# SAU-G0-EX_AHT-GL.net
KiCad netlist of a schematic drawn in Altium Designer
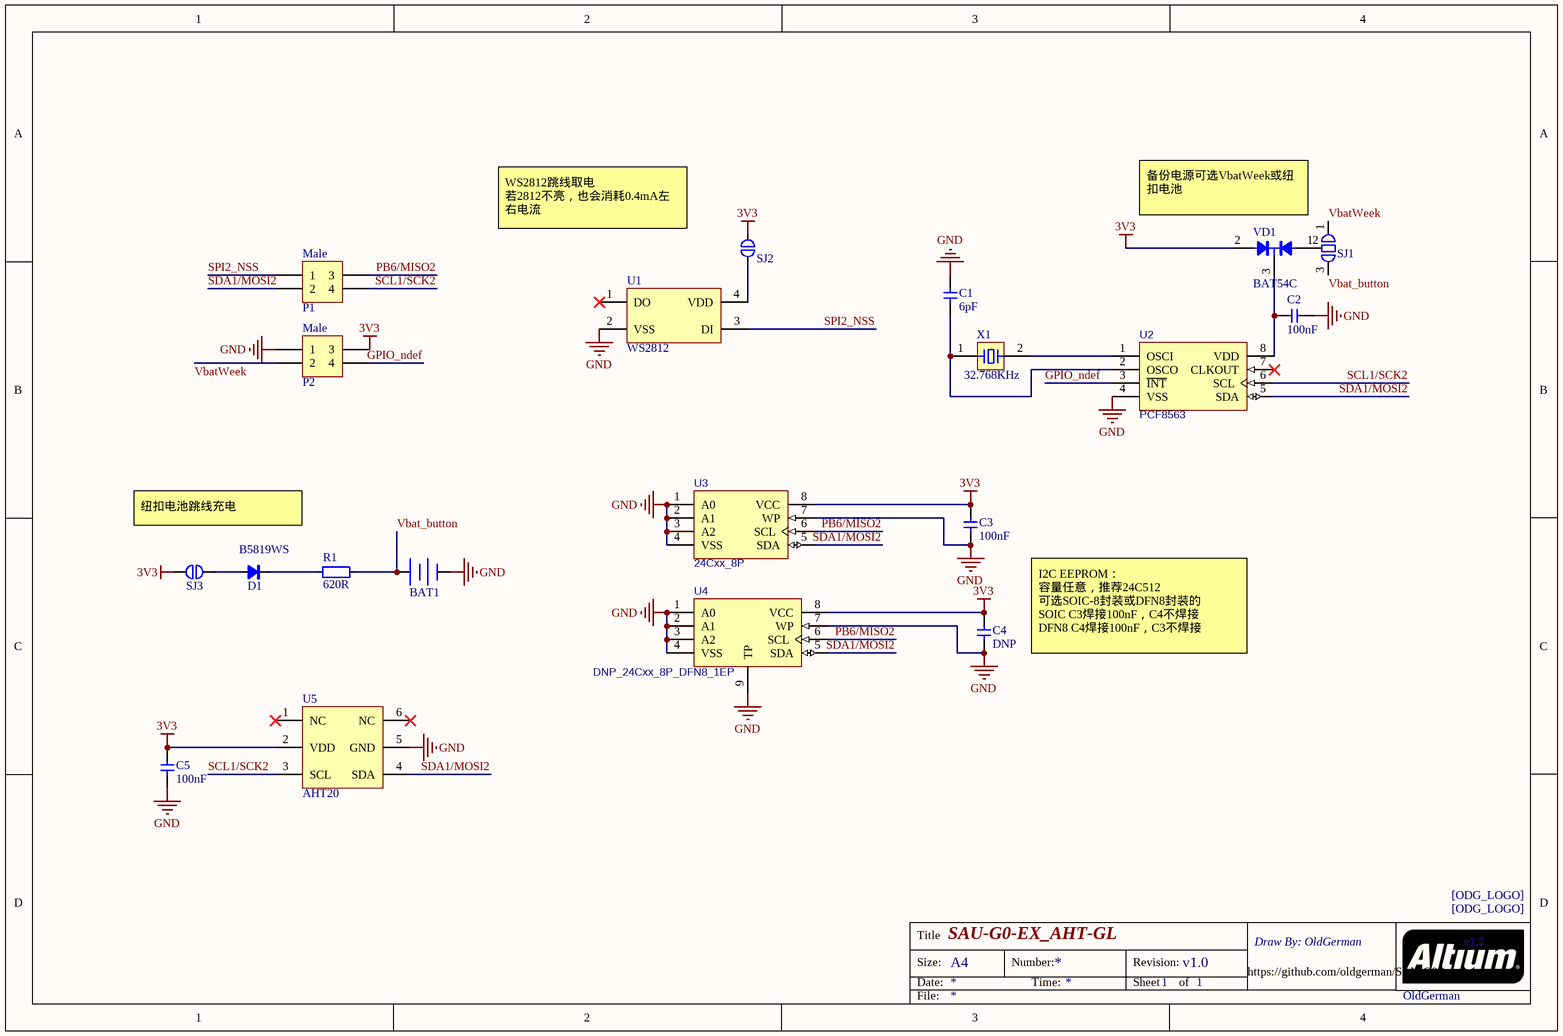
[diagram p0: SAU-G0-EX_AHT-GL.SchDoc]

(export (version "E")
  (design (tool "Eeschema 10.0.6"))
  (components
    (comp (ref "BAT1")
      (value "BAT")
      (footprint "MS621FE-FL11E")
      (description "锂电池")
      (libsource (lib "ODG_AD_Lib") (part "BAT"))
    )
    (comp (ref "C1")
      (value "6pF")
      (footprint "C0603")
      (description "Capacitor")
      (libsource (lib "ODG_AD_Lib") (part "CAP"))
    )
    (comp (ref "C2")
      (value "100nF")
      (footprint "C0603")
      (description "Capacitor")
      (libsource (lib "ODG_AD_Lib") (part "CAP"))
    )
    (comp (ref "C3")
      (value "100nF")
      (footprint "C0603")
      (description "Capacitor")
      (libsource (lib "ODG_AD_Lib") (part "CAP"))
    )
    (comp (ref "C4")
      (value "DNP")
      (footprint "C0402")
      (description "Capacitor")
      (libsource (lib "ODG_AD_Lib") (part "CAP"))
    )
    (comp (ref "C5")
      (value "100nF")
      (footprint "C0603")
      (description "Capacitor")
      (libsource (lib "ODG_AD_Lib") (part "CAP"))
    )
    (comp (ref "D1")
      (value "B5819WS")
      (footprint "SOD-323")
      (description "二极管")
      (libsource (lib "ODG_AD_Lib") (part "DIODE"))
    )
    (comp (ref "ODG1")
      (value "ODG_LOGO")
      (footprint "ODG_LOGO_soldermask")
      (libsource (lib "ODG_AD_Lib") (part "ODG_LOGO"))
    )
    (comp (ref "ODG2")
      (value "ODG_LOGO")
      (footprint "ODG_LOGO_soldermask")
      (libsource (lib "ODG_AD_Lib") (part "ODG_LOGO"))
    )
    (comp (ref "P1")
      (value "Male")
      (footprint "2.0mm_Male_2x2")
      (libsource (lib "ODG_AD_Lib") (part "CONN_2X2"))
    )
    (comp (ref "P2")
      (value "Male")
      (footprint "2.0mm_Male_2x2")
      (libsource (lib "ODG_AD_Lib") (part "CONN_2X2"))
    )
    (comp (ref "R1")
      (value "620R")
      (footprint "R0603")
      (description "Resistor")
      (libsource (lib "ODG_AD_Lib") (part "RES"))
    )
    (comp (ref "SJ1")
      (value "SJ_3P")
      (footprint "SJ_3P_MINI")
      (description "焊接跳线二选一")
      (libsource (lib "ODG_AD_Lib") (part "SJ_3P"))
    )
    (comp (ref "SJ2")
      (value "SJ_2P")
      (footprint "SJ_2P_MINI")
      (description "焊接跳线")
      (libsource (lib "ODG_AD_Lib") (part "SJ_2P"))
    )
    (comp (ref "SJ3")
      (value "SJ_2P")
      (footprint "SJ_2P_MINI")
      (description "焊接跳线")
      (libsource (lib "") (part "SJ_2P_1"))
    )
    (comp (ref "U1")
      (value "WS2812")
      (footprint "WS2812_2020")
      (libsource (lib "ODG_AD_Lib") (part "WS2812"))
    )
    (comp (ref "U2")
      (value "PCF8563")
      (footprint "ANALOG DEV SOIC-8 R8")
      (libsource (lib "ODG_AD_Lib") (part "PCF8563"))
    )
    (comp (ref "U3")
      (value "24Cxx_8P")
      (footprint "ANALOG DEV SOIC-8 R8")
      (libsource (lib "ODG_AD_Lib") (part "24Cxx_8P"))
    )
    (comp (ref "U4")
      (value "DNP_24Cxx_8P_DFN8_1EP")
      (footprint "DFN-8-1EP_3x2mm_P0.5mm_EP1.75x1.45mm")
      (libsource (lib "ODG_AD_Lib") (part "24Cxx_8P_DFN8_1EP"))
    )
    (comp (ref "U5")
      (value "AHT20")
      (footprint "AHT20")
      (description "线性稳压芯片")
      (fields (field (name "版权归属") "源创客"))
      (libsource (lib "ODG_AD_Lib") (part "AHT20"))
    )
    (comp (ref "VD1")
      (value "BAT54C")
      (footprint "DIODES SOT-323-3")
      (description "贴片肖特基二极管")
      (fields (field (name "版权归属") "源创客"))
      (libsource (lib "ODG_AD_Lib") (part "BAT54C"))
    )
    (comp (ref "X1")
      (value "32.768KHz")
      (footprint "XTAL_2P_3215")
      (description "2脚无源石英晶振")
      (fields (field (name "版权归属") "源创客"))
      (libsource (lib "ODG_AD_Lib") (part "XTAL-2P"))
    )
  )
  (nets
    (net (code "1") (name "/GPIO_ndef") (class "Default")
      (node (ref "P2") (pin "4") (pinfunction "4_4") (pintype "passive"))
      (node (ref "U2") (pin "3") (pinfunction "~{INT}_3") (pintype "passive"))
    )
    (net (code "2") (name "/PB6{slash}MISO2") (class "Default")
      (node (ref "P1") (pin "3") (pinfunction "3_3") (pintype "passive"))
      (node (ref "U3") (pin "6") (pinfunction "SCL_6") (pintype "input"))
      (node (ref "U4") (pin "6") (pinfunction "SCL_6") (pintype "input"))
    )
    (net (code "3") (name "/SCL1{slash}SCK2") (class "Default")
      (node (ref "P1") (pin "4") (pinfunction "4_4") (pintype "passive"))
      (node (ref "U2") (pin "6") (pinfunction "SCL_6") (pintype "input"))
      (node (ref "U5") (pin "3") (pinfunction "SCL_3") (pintype "passive"))
    )
    (net (code "4") (name "/SDA1{slash}MOSI2") (class "Default")
      (node (ref "P1") (pin "2") (pinfunction "2_2") (pintype "passive"))
      (node (ref "U2") (pin "5") (pinfunction "SDA_5") (pintype "bidirectional"))
      (node (ref "U3") (pin "5") (pinfunction "SDA_5") (pintype "bidirectional"))
      (node (ref "U4") (pin "5") (pinfunction "SDA_5") (pintype "bidirectional"))
      (node (ref "U5") (pin "4") (pinfunction "SDA_4") (pintype "passive"))
    )
    (net (code "5") (name "/SPI2_NSS") (class "Default")
      (node (ref "P1") (pin "1") (pinfunction "1_1") (pintype "passive"))
      (node (ref "U1") (pin "3") (pinfunction "DI_3") (pintype "passive"))
    )
    (net (code "6") (name "/VbatWeek") (class "Default")
      (node (ref "P2") (pin "2") (pinfunction "2_2") (pintype "passive"))
      (node (ref "SJ1") (pin "1") (pinfunction "1_1") (pintype "passive"))
    )
    (net (code "7") (name "/Vbat_button") (class "Default")
      (node (ref "BAT1") (pin "1") (pinfunction "+_1") (pintype "passive"))
      (node (ref "R1") (pin "2") (pinfunction "2_2") (pintype "passive"))
      (node (ref "SJ1") (pin "3") (pinfunction "3_3") (pintype "passive"))
    )
    (net (code "8") (name "3V3") (class "Default")
      (node (ref "C3") (pin "1") (pinfunction "1_1") (pintype "passive"))
      (node (ref "C4") (pin "1") (pinfunction "1_1") (pintype "passive"))
      (node (ref "C5") (pin "1") (pinfunction "1_1") (pintype "passive"))
      (node (ref "P2") (pin "3") (pinfunction "3_3") (pintype "passive"))
      (node (ref "SJ2") (pin "1") (pinfunction "1_1") (pintype "passive"))
      (node (ref "SJ3") (pin "2") (pinfunction "2_2") (pintype "passive"))
      (node (ref "U3") (pin "8") (pinfunction "VCC_8") (pintype "passive"))
      (node (ref "U4") (pin "8") (pinfunction "VCC_8") (pintype "passive"))
      (node (ref "U5") (pin "2") (pinfunction "VDD_2") (pintype "passive"))
      (node (ref "VD1") (pin "2") (pinfunction "2_2") (pintype "passive"))
    )
    (net (code "9") (name "GND") (class "Default")
      (node (ref "BAT1") (pin "2") (pinfunction "-_2") (pintype "passive"))
      (node (ref "C1") (pin "1") (pinfunction "1_1") (pintype "passive"))
      (node (ref "C2") (pin "2") (pinfunction "2_2") (pintype "passive"))
      (node (ref "C3") (pin "2") (pinfunction "2_2") (pintype "passive"))
      (node (ref "C4") (pin "2") (pinfunction "2_2") (pintype "passive"))
      (node (ref "C5") (pin "2") (pinfunction "2_2") (pintype "passive"))
      (node (ref "P2") (pin "1") (pinfunction "1_1") (pintype "passive"))
      (node (ref "U1") (pin "2") (pinfunction "VSS_2") (pintype "passive"))
      (node (ref "U2") (pin "4") (pinfunction "VSS_4") (pintype "passive"))
      (node (ref "U3") (pin "1") (pinfunction "A0_1") (pintype "passive"))
      (node (ref "U3") (pin "2") (pinfunction "A1_2") (pintype "passive"))
      (node (ref "U3") (pin "3") (pinfunction "A2_3") (pintype "passive"))
      (node (ref "U3") (pin "4") (pinfunction "VSS_4") (pintype "passive"))
      (node (ref "U3") (pin "7") (pinfunction "WP_7") (pintype "input"))
      (node (ref "U4") (pin "1") (pinfunction "A0_1") (pintype "passive"))
      (node (ref "U4") (pin "2") (pinfunction "A1_2") (pintype "passive"))
      (node (ref "U4") (pin "3") (pinfunction "A2_3") (pintype "passive"))
      (node (ref "U4") (pin "4") (pinfunction "VSS_4") (pintype "passive"))
      (node (ref "U4") (pin "7") (pinfunction "WP_7") (pintype "input"))
      (node (ref "U4") (pin "9") (pinfunction "TP_9") (pintype "passive"))
      (node (ref "U5") (pin "5") (pinfunction "GND_5") (pintype "passive"))
    )
    (net (code "10") (name "Net-(D1-A)") (class "Default")
      (node (ref "D1") (pin "1") (pinfunction "A_1") (pintype "passive"))
      (node (ref "SJ3") (pin "1") (pinfunction "1_1") (pintype "passive"))
    )
    (net (code "11") (name "Net-(D1-C)") (class "Default")
      (node (ref "D1") (pin "2") (pinfunction "C_2") (pintype "passive"))
      (node (ref "R1") (pin "1") (pinfunction "1_1") (pintype "passive"))
    )
    (net (code "12") (name "Net-(SJ1-Pad2)") (class "Default")
      (node (ref "SJ1") (pin "2") (pinfunction "2_2") (pintype "passive"))
      (node (ref "VD1") (pin "1") (pinfunction "1_1") (pintype "passive"))
    )
    (net (code "13") (name "Net-(U1-VDD)") (class "Default")
      (node (ref "SJ2") (pin "2") (pinfunction "2_2") (pintype "passive"))
      (node (ref "U1") (pin "4") (pinfunction "VDD_4") (pintype "passive"))
    )
    (net (code "14") (name "Net-(U2-OSCI)") (class "Default")
      (node (ref "U2") (pin "1") (pinfunction "OSCI_1") (pintype "passive"))
      (node (ref "X1") (pin "2") (pinfunction "2_2") (pintype "passive"))
    )
    (net (code "15") (name "Net-(U2-OSCO)") (class "Default")
      (node (ref "C1") (pin "2") (pinfunction "2_2") (pintype "passive"))
      (node (ref "U2") (pin "2") (pinfunction "OSCO_2") (pintype "passive"))
      (node (ref "X1") (pin "1") (pinfunction "1_1") (pintype "passive"))
    )
    (net (code "16") (name "Net-(U2-VDD)") (class "Default")
      (node (ref "C2") (pin "1") (pinfunction "1_1") (pintype "passive"))
      (node (ref "U2") (pin "8") (pinfunction "VDD_8") (pintype "passive"))
      (node (ref "VD1") (pin "3") (pinfunction "3_3") (pintype "passive"))
    )
    (net (code "17") (name "unconnected-(U1-DO-Pad1)") (class "Default")
      (node (ref "U1") (pin "1") (pinfunction "DO_1") (pintype "passive+no_connect"))
    )
    (net (code "18") (name "unconnected-(U2-CLKOUT-Pad7)") (class "Default")
      (node (ref "U2") (pin "7") (pinfunction "CLKOUT_7") (pintype "input+no_connect"))
    )
    (net (code "19") (name "unconnected-(U5-NC-Pad1)") (class "Default")
      (node (ref "U5") (pin "1") (pinfunction "NC_1") (pintype "passive+no_connect"))
    )
    (net (code "20") (name "unconnected-(U5-NC-Pad6)") (class "Default")
      (node (ref "U5") (pin "6") (pinfunction "NC_6") (pintype "passive+no_connect"))
    )
  )
)
